# ContactlessCon.net
KiCad netlist of a schematic drawn in EAGLE
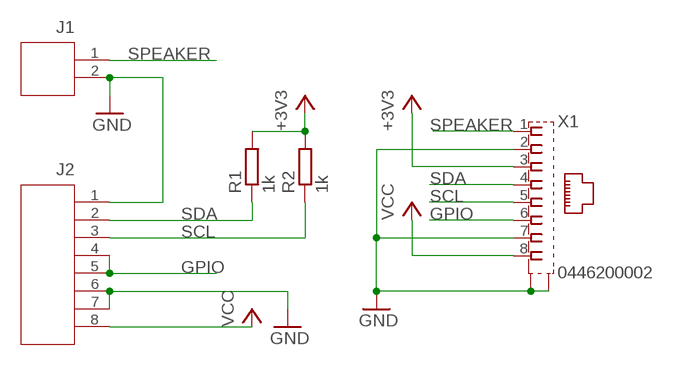
[diagram p0: schematic, sheet 1]

(export (version "E")
  (design (tool "Eeschema 10.0.6"))
  (components
    (comp (ref "J1")
      (value "PINHEADER-212*1")
      (footprint "eagle-import:PINHEADER-2_1")
      (libsource (lib "eagle-import") (part "PINHEADER-2121"))
    )
    (comp (ref "J2")
      (value "PINHEADER-818*1")
      (footprint "eagle-import:PINHEADER-8_1")
      (libsource (lib "eagle-import") (part "PINHEADER-8181"))
    )
    (comp (ref "R1")
      (value "1k")
      (footprint "eagle-import:R1206")
      (libsource (lib "eagle-import") (part "R-EU_R1206"))
    )
    (comp (ref "R2")
      (value "1k")
      (footprint "eagle-import:R1206")
      (libsource (lib "eagle-import") (part "R-EU_R1206"))
    )
    (comp (ref "X1")
      (value "0446200002")
      (footprint "eagle-import:0446200002")
      (fields (field (name "MF") "MOLEX"))
      (libsource (lib "eagle-import") (part "0446200002"))
    )
  )
  (nets
    (net (code "1") (name "+3V3") (class "Default")
      (node (ref "R1") (pin "2") (pinfunction "2_2") (pintype "passive"))
      (node (ref "R2") (pin "2") (pinfunction "2_2") (pintype "passive"))
      (node (ref "X1") (pin "3") (pinfunction "3_3") (pintype "passive"))
    )
    (net (code "2") (name "/GPIO") (class "Default")
      (node (ref "J2") (pin "4") (pinfunction "4_4") (pintype "bidirectional"))
      (node (ref "J2") (pin "5") (pinfunction "5_5") (pintype "bidirectional"))
      (node (ref "X1") (pin "6") (pinfunction "6_6") (pintype "passive"))
    )
    (net (code "3") (name "/SCL") (class "Default")
      (node (ref "J2") (pin "3") (pinfunction "3_3") (pintype "bidirectional"))
      (node (ref "R2") (pin "1") (pinfunction "1_1") (pintype "passive"))
      (node (ref "X1") (pin "5") (pinfunction "5_5") (pintype "passive"))
    )
    (net (code "4") (name "/SDA") (class "Default")
      (node (ref "J2") (pin "2") (pinfunction "2_2") (pintype "bidirectional"))
      (node (ref "R1") (pin "1") (pinfunction "1_1") (pintype "passive"))
      (node (ref "X1") (pin "4") (pinfunction "4_4") (pintype "passive"))
    )
    (net (code "5") (name "/SPEAKER") (class "Default")
      (node (ref "J1") (pin "1") (pinfunction "1_1") (pintype "bidirectional"))
      (node (ref "X1") (pin "1") (pinfunction "1_1") (pintype "passive"))
    )
    (net (code "6") (name "GND") (class "Default")
      (node (ref "J1") (pin "2") (pinfunction "2_2") (pintype "bidirectional"))
      (node (ref "J2") (pin "1") (pinfunction "1_1") (pintype "bidirectional"))
      (node (ref "J2") (pin "6") (pinfunction "6_6") (pintype "bidirectional"))
      (node (ref "J2") (pin "7") (pinfunction "7_7") (pintype "bidirectional"))
      (node (ref "X1") (pin "2") (pinfunction "2_2") (pintype "passive"))
      (node (ref "X1") (pin "7") (pinfunction "7_7") (pintype "passive"))
      (node (ref "X1") (pin "S@1") (pinfunction "S1_S@1") (pintype "passive"))
      (node (ref "X1") (pin "S@2") (pinfunction "S2_S@2") (pintype "passive"))
    )
    (net (code "7") (name "VCC") (class "Default")
      (node (ref "J2") (pin "8") (pinfunction "8_8") (pintype "bidirectional"))
      (node (ref "X1") (pin "8") (pinfunction "8_8") (pintype "passive"))
    )
  )
)
